# 2wd.net
KiCad netlist of a schematic drawn in EAGLE
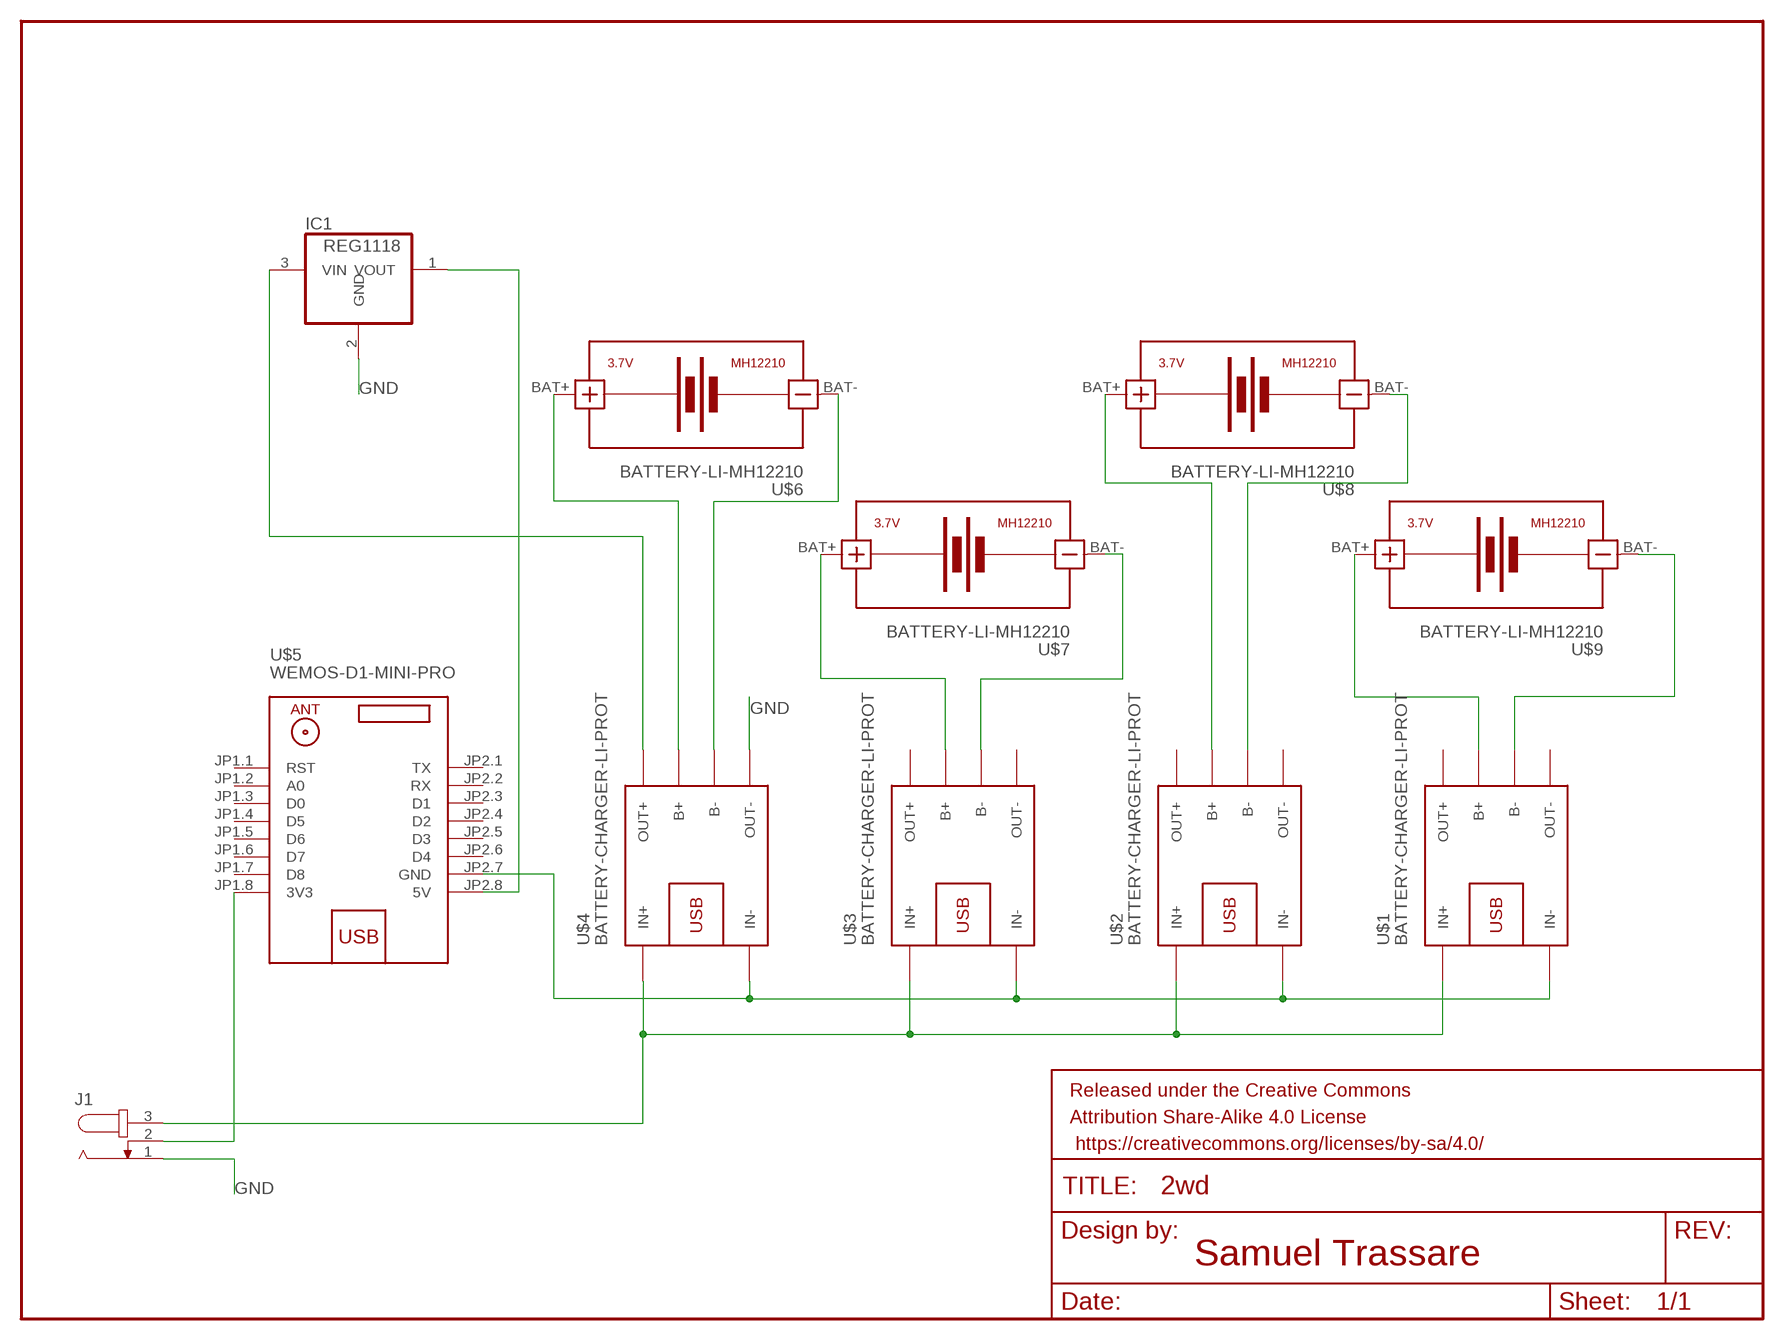
[diagram p0: schematic, sheet 1]

(export (version "E")
  (design (tool "Eeschema 10.0.6"))
  (components
    (comp (ref "FRAME1")
      (value "FRAME-LETTER")
      (footprint "eagle-import:CREATIVE_COMMONS")
      (libsource (lib "eagle-import") (part "FRAME-LETTER"))
    )
    (comp (ref "IC1")
      (value "REG1118")
      (footprint "eagle-import:SOT223")
      (fields (field (name "MPN") "REG1118-2.85/2K5G4"))
      (libsource (lib "eagle-import") (part "REG1118"))
    )
    (comp (ref "J1")
      (value "JACK-PLUG0")
      (footprint "eagle-import:SPC4077")
      (libsource (lib "eagle-import") (part "JACK-PLUG0"))
    )
    (comp (ref "U$1")
      (value "BATTERY-CHARGER-LI-PROT")
      (footprint "eagle-import:BATTERY-CHARGER-LI-PROT")
      (libsource (lib "eagle-import") (part "BATTERY-CHARGER-LI-PROT"))
    )
    (comp (ref "U$2")
      (value "BATTERY-CHARGER-LI-PROT")
      (footprint "eagle-import:BATTERY-CHARGER-LI-PROT")
      (libsource (lib "eagle-import") (part "BATTERY-CHARGER-LI-PROT"))
    )
    (comp (ref "U$3")
      (value "BATTERY-CHARGER-LI-PROT")
      (footprint "eagle-import:BATTERY-CHARGER-LI-PROT")
      (libsource (lib "eagle-import") (part "BATTERY-CHARGER-LI-PROT"))
    )
    (comp (ref "U$4")
      (value "BATTERY-CHARGER-LI-PROT")
      (footprint "eagle-import:BATTERY-CHARGER-LI-PROT")
      (libsource (lib "eagle-import") (part "BATTERY-CHARGER-LI-PROT"))
    )
    (comp (ref "U$5")
      (value "WEMOS-D1-MINI-PRO")
      (footprint "eagle-import:WEMOS-D1-MINI-PRO")
      (libsource (lib "eagle-import") (part "WEMOS-D1-MINI-PRO"))
    )
    (comp (ref "U$6")
      (value "BATTERY-LI-MH12210")
      (footprint "eagle-import:BATTERY-LI-MH12210")
      (libsource (lib "eagle-import") (part "BATTERY-LI-MH12210"))
    )
    (comp (ref "U$7")
      (value "BATTERY-LI-MH12210")
      (footprint "eagle-import:BATTERY-LI-MH12210")
      (libsource (lib "eagle-import") (part "BATTERY-LI-MH12210"))
    )
    (comp (ref "U$8")
      (value "BATTERY-LI-MH12210")
      (footprint "eagle-import:BATTERY-LI-MH12210")
      (libsource (lib "eagle-import") (part "BATTERY-LI-MH12210"))
    )
    (comp (ref "U$9")
      (value "BATTERY-LI-MH12210")
      (footprint "eagle-import:BATTERY-LI-MH12210")
      (libsource (lib "eagle-import") (part "BATTERY-LI-MH12210"))
    )
  )
  (nets
    (net (code "1") (name "/GND") (class "Default")
      (node (ref "IC1") (pin "2") (pinfunction "GND_2") (pintype "power_in"))
      (node (ref "J1") (pin "1") (pinfunction "1_1") (pintype "passive"))
      (node (ref "U$1") (pin "IN-") (pinfunction "IN-_IN-") (pintype "bidirectional"))
      (node (ref "U$2") (pin "IN-") (pinfunction "IN-_IN-") (pintype "bidirectional"))
      (node (ref "U$3") (pin "IN-") (pinfunction "IN-_IN-") (pintype "bidirectional"))
      (node (ref "U$4") (pin "IN-") (pinfunction "IN-_IN-") (pintype "bidirectional"))
      (node (ref "U$4") (pin "OUT-") (pinfunction "OUT-_OUT-") (pintype "bidirectional"))
      (node (ref "U$5") (pin "JP2.7") (pinfunction "GND_JP2.7") (pintype "power_in"))
    )
    (net (code "2") (name "Net-(IC1-VIN)") (class "Default")
      (node (ref "IC1") (pin "3") (pinfunction "VIN_3") (pintype "input"))
      (node (ref "U$4") (pin "OUT+") (pinfunction "OUT+_OUT+") (pintype "bidirectional"))
    )
    (net (code "3") (name "Net-(IC1-VOUT)") (class "Default")
      (node (ref "IC1") (pin "1") (pinfunction "VOUT_1") (pintype "output"))
      (node (ref "U$5") (pin "JP2.8") (pinfunction "5V_JP2.8") (pintype "power_in"))
    )
    (net (code "4") (name "Net-(J1-Pad3)") (class "Default")
      (node (ref "J1") (pin "3") (pinfunction "3_3") (pintype "passive"))
      (node (ref "U$1") (pin "IN+") (pinfunction "IN+_IN+") (pintype "bidirectional"))
      (node (ref "U$2") (pin "IN+") (pinfunction "IN+_IN+") (pintype "bidirectional"))
      (node (ref "U$3") (pin "IN+") (pinfunction "IN+_IN+") (pintype "bidirectional"))
      (node (ref "U$4") (pin "IN+") (pinfunction "IN+_IN+") (pintype "bidirectional"))
    )
    (net (code "5") (name "Net-(U$1-PadB+)") (class "Default")
      (node (ref "U$1") (pin "B+") (pinfunction "B+_B+") (pintype "bidirectional"))
      (node (ref "U$9") (pin "BAT+") (pinfunction "BAT+_BAT+") (pintype "power_in"))
    )
    (net (code "6") (name "Net-(U$1-PadB-)") (class "Default")
      (node (ref "U$1") (pin "B-") (pinfunction "B-_B-") (pintype "bidirectional"))
      (node (ref "U$9") (pin "BAT-") (pinfunction "BAT-_BAT-") (pintype "power_in"))
    )
    (net (code "7") (name "Net-(U$2-PadB+)") (class "Default")
      (node (ref "U$2") (pin "B+") (pinfunction "B+_B+") (pintype "bidirectional"))
      (node (ref "U$8") (pin "BAT+") (pinfunction "BAT+_BAT+") (pintype "power_in"))
    )
    (net (code "8") (name "Net-(U$2-PadB-)") (class "Default")
      (node (ref "U$2") (pin "B-") (pinfunction "B-_B-") (pintype "bidirectional"))
      (node (ref "U$8") (pin "BAT-") (pinfunction "BAT-_BAT-") (pintype "power_in"))
    )
    (net (code "9") (name "Net-(U$3-PadB+)") (class "Default")
      (node (ref "U$3") (pin "B+") (pinfunction "B+_B+") (pintype "bidirectional"))
      (node (ref "U$7") (pin "BAT+") (pinfunction "BAT+_BAT+") (pintype "power_in"))
    )
    (net (code "10") (name "Net-(U$3-PadB-)") (class "Default")
      (node (ref "U$3") (pin "B-") (pinfunction "B-_B-") (pintype "bidirectional"))
      (node (ref "U$7") (pin "BAT-") (pinfunction "BAT-_BAT-") (pintype "power_in"))
    )
    (net (code "11") (name "Net-(U$4-PadB+)") (class "Default")
      (node (ref "U$4") (pin "B+") (pinfunction "B+_B+") (pintype "bidirectional"))
      (node (ref "U$6") (pin "BAT+") (pinfunction "BAT+_BAT+") (pintype "power_in"))
    )
    (net (code "12") (name "Net-(U$4-PadB-)") (class "Default")
      (node (ref "U$4") (pin "B-") (pinfunction "B-_B-") (pintype "bidirectional"))
      (node (ref "U$6") (pin "BAT-") (pinfunction "BAT-_BAT-") (pintype "power_in"))
    )
    (net (code "13") (name "Net-(U$5-3V3)") (class "Default")
      (node (ref "J1") (pin "2") (pinfunction "2_2") (pintype "passive"))
      (node (ref "U$5") (pin "JP1.8") (pinfunction "3V3_JP1.8") (pintype "power_in"))
    )
    (net (code "14") (name "unconnected-(U$1-PadOUT+)") (class "Default")
      (node (ref "U$1") (pin "OUT+") (pinfunction "OUT+_OUT+") (pintype "bidirectional"))
    )
    (net (code "15") (name "unconnected-(U$1-PadOUT-)") (class "Default")
      (node (ref "U$1") (pin "OUT-") (pinfunction "OUT-_OUT-") (pintype "bidirectional"))
    )
    (net (code "16") (name "unconnected-(U$2-PadOUT+)") (class "Default")
      (node (ref "U$2") (pin "OUT+") (pinfunction "OUT+_OUT+") (pintype "bidirectional"))
    )
    (net (code "17") (name "unconnected-(U$2-PadOUT-)") (class "Default")
      (node (ref "U$2") (pin "OUT-") (pinfunction "OUT-_OUT-") (pintype "bidirectional"))
    )
    (net (code "18") (name "unconnected-(U$3-PadOUT+)") (class "Default")
      (node (ref "U$3") (pin "OUT+") (pinfunction "OUT+_OUT+") (pintype "bidirectional"))
    )
    (net (code "19") (name "unconnected-(U$3-PadOUT-)") (class "Default")
      (node (ref "U$3") (pin "OUT-") (pinfunction "OUT-_OUT-") (pintype "bidirectional"))
    )
    (net (code "20") (name "unconnected-(U$5-A0-PadJP1.2)") (class "Default")
      (node (ref "U$5") (pin "JP1.2") (pinfunction "A0_JP1.2") (pintype "bidirectional"))
    )
    (net (code "21") (name "unconnected-(U$5-D0-PadJP1.3)") (class "Default")
      (node (ref "U$5") (pin "JP1.3") (pinfunction "D0_JP1.3") (pintype "bidirectional"))
    )
    (net (code "22") (name "unconnected-(U$5-D1-PadJP2.3)") (class "Default")
      (node (ref "U$5") (pin "JP2.3") (pinfunction "D1_JP2.3") (pintype "bidirectional"))
    )
    (net (code "23") (name "unconnected-(U$5-D2-PadJP2.4)") (class "Default")
      (node (ref "U$5") (pin "JP2.4") (pinfunction "D2_JP2.4") (pintype "bidirectional"))
    )
    (net (code "24") (name "unconnected-(U$5-D3-PadJP2.5)") (class "Default")
      (node (ref "U$5") (pin "JP2.5") (pinfunction "D3_JP2.5") (pintype "bidirectional"))
    )
    (net (code "25") (name "unconnected-(U$5-D4-PadJP2.6)") (class "Default")
      (node (ref "U$5") (pin "JP2.6") (pinfunction "D4_JP2.6") (pintype "bidirectional"))
    )
    (net (code "26") (name "unconnected-(U$5-D5-PadJP1.4)") (class "Default")
      (node (ref "U$5") (pin "JP1.4") (pinfunction "D5_JP1.4") (pintype "bidirectional"))
    )
    (net (code "27") (name "unconnected-(U$5-D6-PadJP1.5)") (class "Default")
      (node (ref "U$5") (pin "JP1.5") (pinfunction "D6_JP1.5") (pintype "bidirectional"))
    )
    (net (code "28") (name "unconnected-(U$5-D7-PadJP1.6)") (class "Default")
      (node (ref "U$5") (pin "JP1.6") (pinfunction "D7_JP1.6") (pintype "bidirectional"))
    )
    (net (code "29") (name "unconnected-(U$5-D8-PadJP1.7)") (class "Default")
      (node (ref "U$5") (pin "JP1.7") (pinfunction "D8_JP1.7") (pintype "bidirectional"))
    )
    (net (code "30") (name "unconnected-(U$5-RST-PadJP1.1)") (class "Default")
      (node (ref "U$5") (pin "JP1.1") (pinfunction "RST_JP1.1") (pintype "bidirectional"))
    )
    (net (code "31") (name "unconnected-(U$5-RX-PadJP2.2)") (class "Default")
      (node (ref "U$5") (pin "JP2.2") (pinfunction "RX_JP2.2") (pintype "bidirectional"))
    )
    (net (code "32") (name "unconnected-(U$5-TX-PadJP2.1)") (class "Default")
      (node (ref "U$5") (pin "JP2.1") (pinfunction "TX_JP2.1") (pintype "bidirectional"))
    )
  )
)
